# USB_UART.net
KiCad netlist of a schematic drawn in Altium Designer
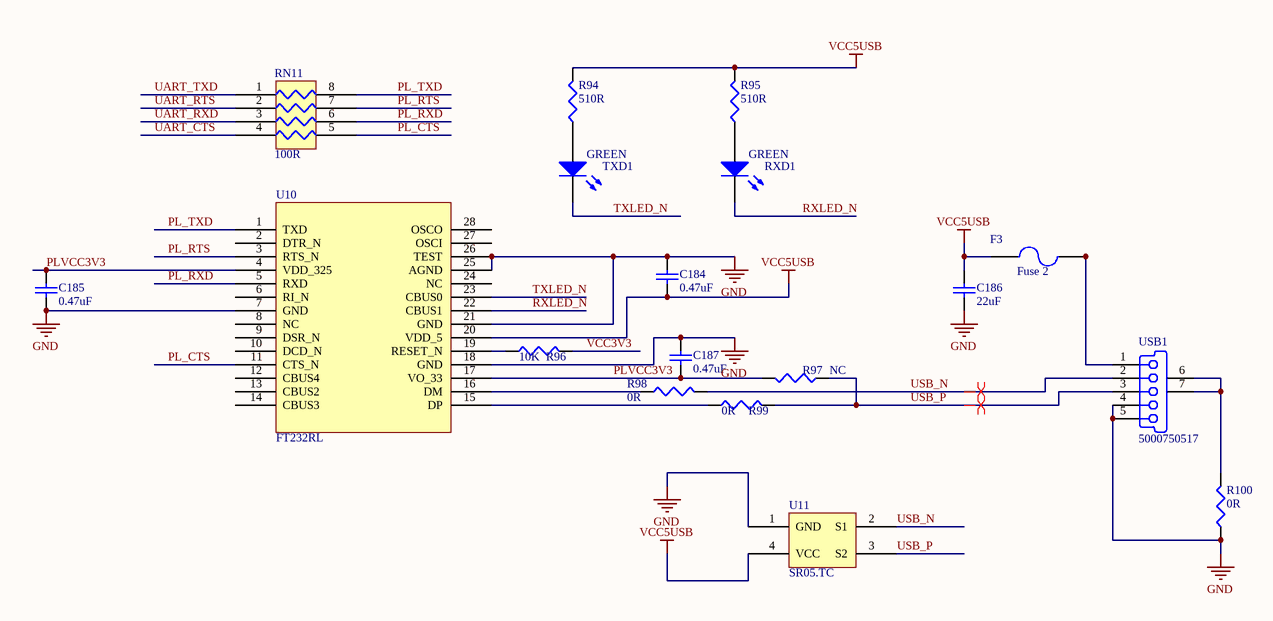
[diagram p0: USB_UART.SchDoc]

(export (version "E")
  (design (tool "Eeschema 10.0.6"))
  (components
    (comp (ref "C184")
      (value "0.47uF")
      (footprint "CAPC1005N")
      (description "Capacitor (Semiconductor SIM Model)")
      (fields (field (name "PUBLISHER") "Altium Limited"))
      (libsource (lib "Miscellaneous Devices") (part "Cap Semi"))
    )
    (comp (ref "C185")
      (value "0.47uF")
      (footprint "CAPC1005N")
      (description "Capacitor (Semiconductor SIM Model)")
      (fields (field (name "PUBLISHER") "Altium Limited"))
      (libsource (lib "Miscellaneous Devices") (part "Cap Semi"))
    )
    (comp (ref "C186")
      (value "22uF")
      (footprint "CAPC3216N")
      (description "Capacitor (Semiconductor SIM Model)")
      (fields (field (name "PUBLISHER") "Altium Limited"))
      (libsource (lib "Miscellaneous Devices") (part "Cap Semi"))
    )
    (comp (ref "C187")
      (value "0.47uF")
      (footprint "CAPC1005N")
      (description "Capacitor (Semiconductor SIM Model)")
      (fields (field (name "PUBLISHER") "Altium Limited"))
      (libsource (lib "Miscellaneous Devices") (part "Cap Semi"))
    )
    (comp (ref "F3")
      (value "Fuse 2")
      (footprint "RESC3216N")
      (description "Fuse")
      (fields (field (name "PUBLISHER") "Altium Limited"))
      (libsource (lib "Miscellaneous Devices") (part "Fuse 2"))
    )
    (comp (ref "R94")
      (value "510R")
      (footprint "RESC1005N")
      (description "Resistor")
      (fields (field (name "PUBLISHER") "Altium Limited"))
      (libsource (lib "Miscellaneous Devices") (part "Res3"))
    )
    (comp (ref "R95")
      (value "510R")
      (footprint "RESC1005N")
      (description "Resistor")
      (fields (field (name "PUBLISHER") "Altium Limited"))
      (libsource (lib "Miscellaneous Devices") (part "Res3"))
    )
    (comp (ref "R96")
      (value "10K")
      (footprint "RESC1005N")
      (description "Resistor")
      (fields (field (name "PUBLISHER") "Altium Limited"))
      (libsource (lib "Miscellaneous Devices") (part "Res3"))
    )
    (comp (ref "R97")
      (value "NC")
      (footprint "RESC1005N")
      (description "Resistor")
      (fields (field (name "PUBLISHER") "Altium Limited"))
      (libsource (lib "Miscellaneous Devices") (part "Res3"))
    )
    (comp (ref "R98")
      (value "0R")
      (footprint "RESC1005N")
      (description "Resistor")
      (fields (field (name "PUBLISHER") "Altium Limited"))
      (libsource (lib "Miscellaneous Devices") (part "Res3"))
    )
    (comp (ref "R99")
      (value "0R")
      (footprint "RESC1005N")
      (description "Resistor")
      (fields (field (name "PUBLISHER") "Altium Limited"))
      (libsource (lib "Miscellaneous Devices") (part "Res3"))
    )
    (comp (ref "R100")
      (value "0R")
      (footprint "RESC1608N")
      (description "Resistor")
      (fields (field (name "PUBLISHER") "Altium Limited"))
      (libsource (lib "Miscellaneous Devices") (part "Res3"))
    )
    (comp (ref "RN11") (value "100R") (footprint "EXBV8V") (libsource (lib "S6") (part "RES4PACK")))
    (comp (ref "RXD1")
      (value "GREEN")
      (footprint "CD1608-0603")
      (description "Typical BLUE SiC LED")
      (fields (field (name "PUBLISHER") "Altium Limited"))
      (libsource (lib "Miscellaneous Devices") (part "LED3"))
    )
    (comp (ref "TXD1")
      (value "GREEN")
      (footprint "CD1608-0603")
      (description "Typical BLUE SiC LED")
      (fields (field (name "PUBLISHER") "Altium Limited"))
      (libsource (lib "Miscellaneous Devices") (part "LED3"))
    )
    (comp (ref "U10") (value "FT232RL") (footprint "SSOP28_N") (libsource (lib "S6_2") (part "FT232RL")))
    (comp (ref "U11") (value "SR05.TC") (footprint "SOT-143_N") (libsource (lib "DS2411") (part "SR05")))
    (comp (ref "USB1")
      (value "5000750517")
      (footprint "548190519")
      (fields (field (name "PUBLISHER") "Altium Limited"))
      (libsource (lib "Molex Serial Bus Mini USB") (part "5000750517"))
    )
  )
  (nets
    (net (code "1") (name "/PLVCC3V3") (class "Default")
      (node (ref "C185") (pin "2") (pinfunction "2_2") (pintype "passive"))
      (node (ref "C187") (pin "1") (pinfunction "1_1") (pintype "passive"))
      (node (ref "R97") (pin "2") (pinfunction "2_2") (pintype "passive"))
      (node (ref "U10") (pin "17") (pinfunction "VO_33_17") (pintype "power_in"))
      (node (ref "U10") (pin "4") (pinfunction "VDD_325_4") (pintype "power_in"))
    )
    (net (code "2") (name "/PL_CTS") (class "Default")
      (node (ref "RN11") (pin "5") (pinfunction "5_5") (pintype "power_in"))
      (node (ref "U10") (pin "11") (pinfunction "CTS_N_11") (pintype "power_in"))
    )
    (net (code "3") (name "/PL_RTS") (class "Default")
      (node (ref "RN11") (pin "7") (pinfunction "7_7") (pintype "power_in"))
      (node (ref "U10") (pin "3") (pinfunction "RTS_N_3") (pintype "power_in"))
    )
    (net (code "4") (name "/PL_RXD") (class "Default")
      (node (ref "RN11") (pin "6") (pinfunction "6_6") (pintype "power_in"))
      (node (ref "U10") (pin "5") (pinfunction "RXD_5") (pintype "power_in"))
    )
    (net (code "5") (name "/PL_TXD") (class "Default")
      (node (ref "RN11") (pin "8") (pinfunction "8_8") (pintype "power_in"))
      (node (ref "U10") (pin "1") (pinfunction "TXD_1") (pintype "power_in"))
    )
    (net (code "6") (name "/RXLED_N") (class "Default")
      (node (ref "RXD1") (pin "2") (pinfunction "K_2") (pintype "passive"))
      (node (ref "U10") (pin "22") (pinfunction "CBUS1_22") (pintype "power_in"))
    )
    (net (code "7") (name "/TXLED_N") (class "Default")
      (node (ref "TXD1") (pin "2") (pinfunction "K_2") (pintype "passive"))
      (node (ref "U10") (pin "23") (pinfunction "CBUS0_23") (pintype "power_in"))
    )
    (net (code "8") (name "/UART_CTS") (class "Default")
      (node (ref "RN11") (pin "4") (pinfunction "4_4") (pintype "power_in"))
    )
    (net (code "9") (name "/UART_RTS") (class "Default")
      (node (ref "RN11") (pin "2") (pinfunction "2_2") (pintype "power_in"))
    )
    (net (code "10") (name "/UART_RXD") (class "Default")
      (node (ref "RN11") (pin "3") (pinfunction "3_3") (pintype "power_in"))
    )
    (net (code "11") (name "/UART_TXD") (class "Default")
      (node (ref "RN11") (pin "1") (pinfunction "1_1") (pintype "power_in"))
    )
    (net (code "12") (name "/USB_N") (class "Default")
      (node (ref "R98") (pin "2") (pinfunction "2_2") (pintype "passive"))
      (node (ref "U11") (pin "2") (pinfunction "S1_2") (pintype "passive"))
      (node (ref "USB1") (pin "2") (pinfunction "D-_2") (pintype "passive"))
    )
    (net (code "13") (name "/USB_P") (class "Default")
      (node (ref "R97") (pin "1") (pinfunction "1_1") (pintype "passive"))
      (node (ref "R99") (pin "2") (pinfunction "2_2") (pintype "passive"))
      (node (ref "U11") (pin "3") (pinfunction "S2_3") (pintype "passive"))
      (node (ref "USB1") (pin "3") (pinfunction "D+_3") (pintype "passive"))
    )
    (net (code "14") (name "/VCC3V3") (class "Default")
      (node (ref "R96") (pin "2") (pinfunction "2_2") (pintype "passive"))
    )
    (net (code "15") (name "GND") (class "Default")
      (node (ref "C184") (pin "2") (pinfunction "2_2") (pintype "passive"))
      (node (ref "C185") (pin "1") (pinfunction "1_1") (pintype "passive"))
      (node (ref "C186") (pin "1") (pinfunction "1_1") (pintype "passive"))
      (node (ref "C187") (pin "2") (pinfunction "2_2") (pintype "passive"))
      (node (ref "R100") (pin "1") (pinfunction "1_1") (pintype "passive"))
      (node (ref "U10") (pin "18") (pinfunction "GND_18") (pintype "power_in"))
      (node (ref "U10") (pin "21") (pinfunction "GND_21") (pintype "power_in"))
      (node (ref "U10") (pin "25") (pinfunction "AGND_25") (pintype "power_in"))
      (node (ref "U10") (pin "26") (pinfunction "TEST_26") (pintype "power_in"))
      (node (ref "U10") (pin "7") (pinfunction "GND_7") (pintype "power_in"))
      (node (ref "U11") (pin "1") (pinfunction "GND_1") (pintype "power_in"))
      (node (ref "USB1") (pin "4") (pinfunction "ID_4") (pintype "passive"))
      (node (ref "USB1") (pin "5") (pinfunction "GND_5") (pintype "passive"))
    )
    (net (code "16") (name "Net-(RXD1-A)") (class "Default")
      (node (ref "R95") (pin "1") (pinfunction "1_1") (pintype "passive"))
      (node (ref "RXD1") (pin "1") (pinfunction "A_1") (pintype "passive"))
    )
    (net (code "17") (name "Net-(TXD1-A)") (class "Default")
      (node (ref "R94") (pin "1") (pinfunction "1_1") (pintype "passive"))
      (node (ref "TXD1") (pin "1") (pinfunction "A_1") (pintype "passive"))
    )
    (net (code "18") (name "Net-(U10-DM)") (class "Default")
      (node (ref "R98") (pin "1") (pinfunction "1_1") (pintype "passive"))
      (node (ref "U10") (pin "16") (pinfunction "DM_16") (pintype "power_in"))
    )
    (net (code "19") (name "Net-(U10-DP)") (class "Default")
      (node (ref "R99") (pin "1") (pinfunction "1_1") (pintype "passive"))
      (node (ref "U10") (pin "15") (pinfunction "DP_15") (pintype "power_in"))
    )
    (net (code "20") (name "Net-(U10-RESET_N)") (class "Default")
      (node (ref "R96") (pin "1") (pinfunction "1_1") (pintype "passive"))
      (node (ref "U10") (pin "19") (pinfunction "RESET_N_19") (pintype "power_in"))
    )
    (net (code "21") (name "Net-(USB1-MH1)") (class "Default")
      (node (ref "R100") (pin "2") (pinfunction "2_2") (pintype "passive"))
      (node (ref "USB1") (pin "6") (pinfunction "MH1_6") (pintype "passive"))
      (node (ref "USB1") (pin "7") (pinfunction "MH2_7") (pintype "passive"))
    )
    (net (code "22") (name "Net-(USB1-V_BUS)") (class "Default")
      (node (ref "F3") (pin "2") (pinfunction "2_2") (pintype "passive"))
      (node (ref "USB1") (pin "1") (pinfunction "V_BUS_1") (pintype "passive"))
    )
    (net (code "23") (name "VCC5USB") (class "Default")
      (node (ref "C184") (pin "1") (pinfunction "1_1") (pintype "passive"))
      (node (ref "C186") (pin "2") (pinfunction "2_2") (pintype "passive"))
      (node (ref "F3") (pin "1") (pinfunction "1_1") (pintype "passive"))
      (node (ref "R94") (pin "2") (pinfunction "2_2") (pintype "passive"))
      (node (ref "R95") (pin "2") (pinfunction "2_2") (pintype "passive"))
      (node (ref "U10") (pin "20") (pinfunction "VDD_5_20") (pintype "power_in"))
      (node (ref "U11") (pin "4") (pinfunction "VCC_4") (pintype "power_in"))
    )
    (net (code "24") (name "unconnected-(U10-CBUS2-Pad13)") (class "Default")
      (node (ref "U10") (pin "13") (pinfunction "CBUS2_13") (pintype "power_in"))
    )
    (net (code "25") (name "unconnected-(U10-CBUS3-Pad14)") (class "Default")
      (node (ref "U10") (pin "14") (pinfunction "CBUS3_14") (pintype "power_in"))
    )
    (net (code "26") (name "unconnected-(U10-CBUS4-Pad12)") (class "Default")
      (node (ref "U10") (pin "12") (pinfunction "CBUS4_12") (pintype "power_in"))
    )
    (net (code "27") (name "unconnected-(U10-DCD_N-Pad10)") (class "Default")
      (node (ref "U10") (pin "10") (pinfunction "DCD_N_10") (pintype "power_in"))
    )
    (net (code "28") (name "unconnected-(U10-DSR_N-Pad9)") (class "Default")
      (node (ref "U10") (pin "9") (pinfunction "DSR_N_9") (pintype "power_in"))
    )
    (net (code "29") (name "unconnected-(U10-DTR_N-Pad2)") (class "Default")
      (node (ref "U10") (pin "2") (pinfunction "DTR_N_2") (pintype "power_in"))
    )
    (net (code "30") (name "unconnected-(U10-NC-Pad8)") (class "Default")
      (node (ref "U10") (pin "8") (pinfunction "NC_8") (pintype "power_in"))
    )
    (net (code "31") (name "unconnected-(U10-NC-Pad24)") (class "Default")
      (node (ref "U10") (pin "24") (pinfunction "NC_24") (pintype "power_in"))
    )
    (net (code "32") (name "unconnected-(U10-OSCI-Pad27)") (class "Default")
      (node (ref "U10") (pin "27") (pinfunction "OSCI_27") (pintype "power_in"))
    )
    (net (code "33") (name "unconnected-(U10-OSCO-Pad28)") (class "Default")
      (node (ref "U10") (pin "28") (pinfunction "OSCO_28") (pintype "power_in"))
    )
    (net (code "34") (name "unconnected-(U10-RI_N-Pad6)") (class "Default")
      (node (ref "U10") (pin "6") (pinfunction "RI_N_6") (pintype "power_in"))
    )
  )
)
